# SSOT_Breakout_Solar.net
KiCad netlist of a schematic drawn in EAGLE
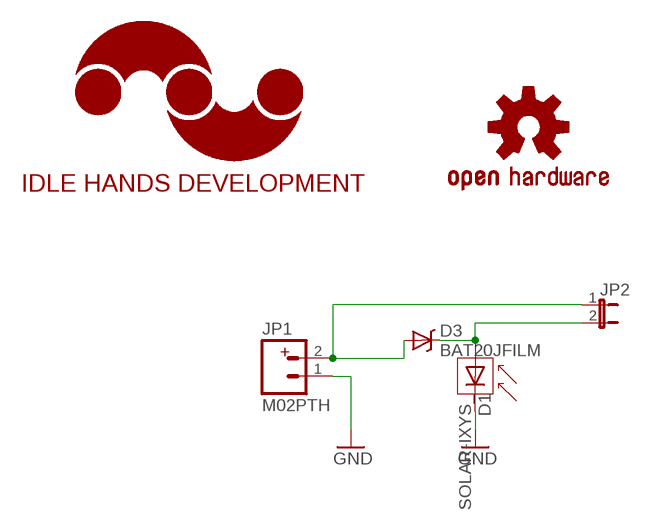
[diagram p0: schematic, sheet 1]

(export (version "E")
  (design (tool "Eeschema 10.0.6"))
  (components
    (comp (ref "D1")
      (value "SOLAR-IXYS_")
      (footprint "eagle-import:SO08")
      (libsource (lib "eagle-import") (part "SOLAR-IXYS_"))
    )
    (comp (ref "D3")
      (value "BAT20JFILM")
      (footprint "eagle-import:SOD-323")
      (libsource (lib "eagle-import") (part "BAT20JFILM"))
    )
    (comp (ref "JP1")
      (value "M02PTH")
      (footprint "eagle-import:1X02")
      (libsource (lib "eagle-import") (part "M02PTH"))
    )
    (comp (ref "JP2")
      (value "JUMPER-2SMD-NO")
      (footprint "eagle-import:SJ_2S-NO")
      (libsource (lib "eagle-import") (part "JUMPER-2SMD-NO"))
    )
    (comp (ref "LOGO1")
      (value "IDLEHANDS_LOGOS")
      (footprint "eagle-import:IHD-LOGO-S")
      (libsource (lib "eagle-import") (part "IDLEHANDS_LOGOS"))
    )
    (comp (ref "LOGO2")
      (value "OSHW-LOGOS")
      (footprint "eagle-import:OSHW-LOGO-S")
      (libsource (lib "eagle-import") (part "OSHW-LOGOS"))
    )
  )
  (nets
    (net (code "1") (name "GND") (class "Default")
      (node (ref "D1") (pin "5") (pinfunction "C_5") (pintype "passive"))
      (node (ref "JP1") (pin "1") (pinfunction "1_1") (pintype "passive"))
    )
    (net (code "2") (name "Net-(D1-A)") (class "Default")
      (node (ref "D1") (pin "8") (pinfunction "A_8") (pintype "passive"))
      (node (ref "D3") (pin "1") (pinfunction "C_1") (pintype "passive"))
      (node (ref "JP2") (pin "2") (pinfunction "2_2") (pintype "passive"))
    )
    (net (code "3") (name "Net-(D3-A)") (class "Default")
      (node (ref "D3") (pin "2") (pinfunction "A_2") (pintype "passive"))
      (node (ref "JP1") (pin "2") (pinfunction "2_2") (pintype "passive"))
      (node (ref "JP2") (pin "1") (pinfunction "1_1") (pintype "passive"))
    )
  )
)
